# sirius1.net
KiCad netlist of a schematic drawn in EAGLE
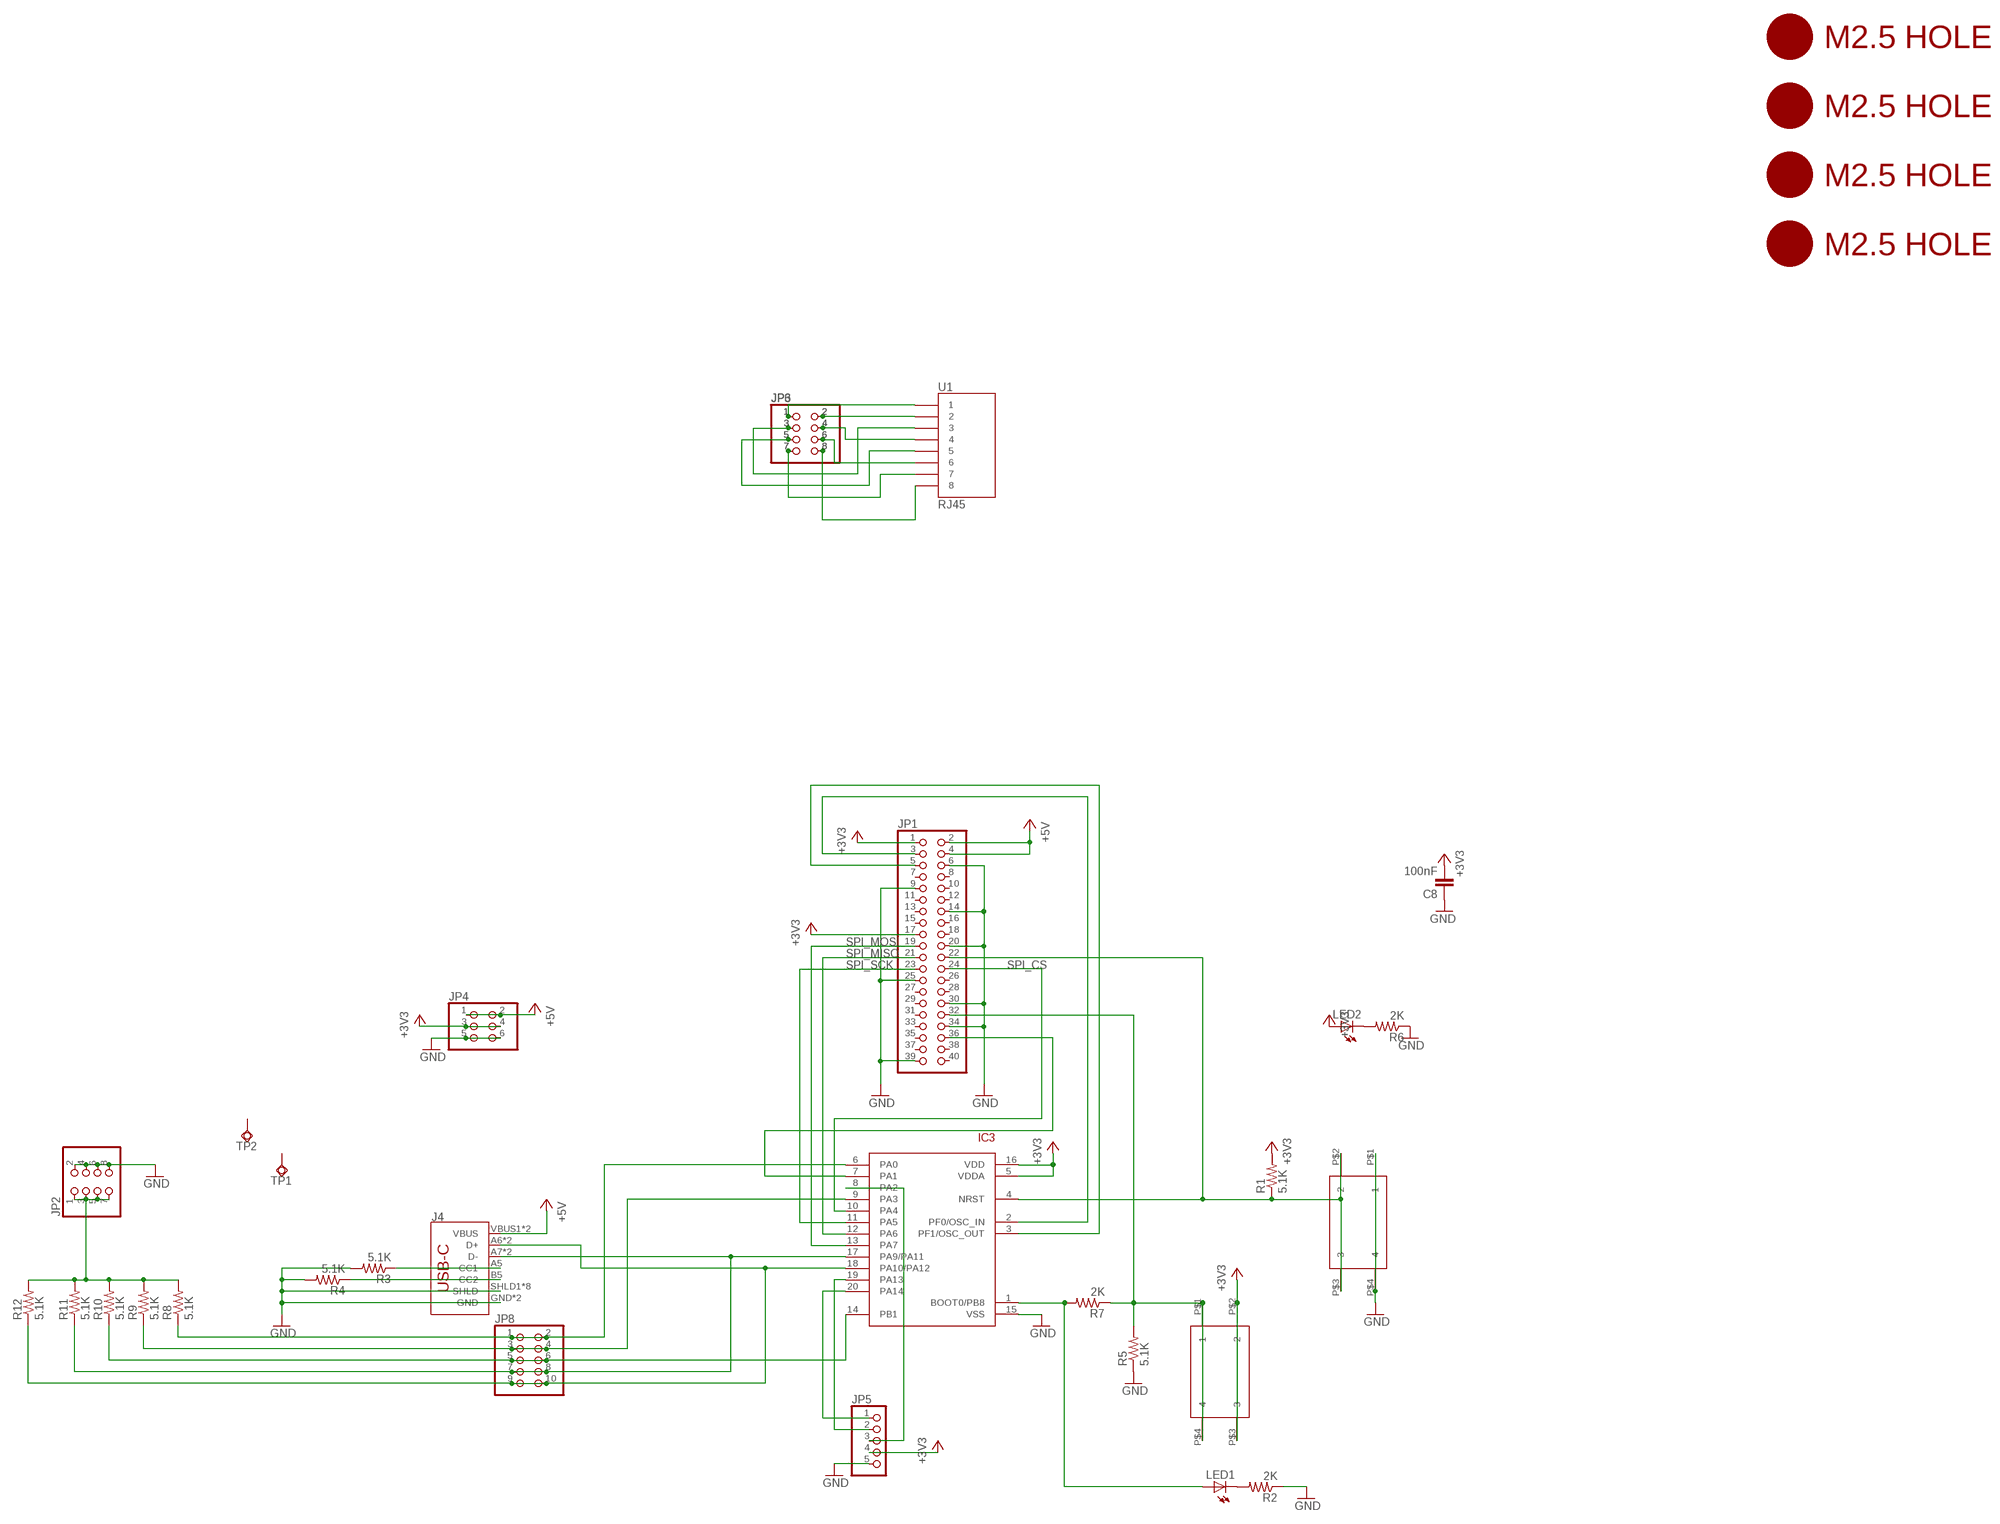
[diagram p0: schematic, sheet 1]

(export (version "E")
  (design (tool "Eeschema 10.0.6"))
  (components
    (comp (ref "C8")
      (value "100nF")
      (footprint "eagle-import:0805@1")
      (libsource (lib "eagle-import") (part "CAP0805"))
    )
    (comp (ref "IC3")
      (value "STM32F042F4")
      (footprint "eagle-import:TSSOP20")
      (libsource (lib "eagle-import") (part "STM32F042F4"))
    )
    (comp (ref "J4")
      (value "USB_C16PIN")
      (footprint "eagle-import:USB-C-16P")
      (libsource (lib "eagle-import") (part "USB_C16PIN"))
    )
    (comp (ref "JP1")
      (value "PINHD-2X20-BIG")
      (footprint "eagle-import:2X20-BIG")
      (libsource (lib "eagle-import") (part "PINHD-2X20-BIG"))
    )
    (comp (ref "JP2")
      (value "PINHD-2X4")
      (footprint "eagle-import:2X04")
      (libsource (lib "eagle-import") (part "PINHD-2X4"))
    )
    (comp (ref "JP3")
      (value "PINHD-2X4")
      (footprint "eagle-import:2X04")
      (libsource (lib "eagle-import") (part "PINHD-2X4"))
    )
    (comp (ref "JP4")
      (value "PINHD-2X3")
      (footprint "eagle-import:2X03")
      (libsource (lib "eagle-import") (part "PINHD-2X3"))
    )
    (comp (ref "JP5")
      (value "PINHD-1X5")
      (footprint "eagle-import:1X05")
      (libsource (lib "eagle-import") (part "PINHD-1X5"))
    )
    (comp (ref "JP6")
      (value "PINHD-2X4")
      (footprint "eagle-import:2X04")
      (libsource (lib "eagle-import") (part "PINHD-2X4"))
    )
    (comp (ref "JP8")
      (value "PINHD-2X5")
      (footprint "eagle-import:2X05")
      (libsource (lib "eagle-import") (part "PINHD-2X5"))
    )
    (comp (ref "LED1")
      (value "LEDCHIP-LED0805")
      (footprint "eagle-import:CHIP-LED0805")
      (libsource (lib "eagle-import") (part "LEDCHIP-LED0805"))
    )
    (comp (ref "LED2")
      (value "LEDCHIP-LED0805")
      (footprint "eagle-import:CHIP-LED0805")
      (libsource (lib "eagle-import") (part "LEDCHIP-LED0805"))
    )
    (comp (ref "R1")
      (value "5.1K")
      (footprint "eagle-import:0805")
      (libsource (lib "eagle-import") (part "RESISTOR0805-RES"))
    )
    (comp (ref "R2")
      (value "2K")
      (footprint "eagle-import:0805")
      (libsource (lib "eagle-import") (part "RESISTOR0805-RES"))
    )
    (comp (ref "R3")
      (value "5.1K")
      (footprint "eagle-import:0805")
      (libsource (lib "eagle-import") (part "RESISTOR0805-RES"))
    )
    (comp (ref "R4")
      (value "5.1K")
      (footprint "eagle-import:0805")
      (libsource (lib "eagle-import") (part "RESISTOR0805-RES"))
    )
    (comp (ref "R5")
      (value "5.1K")
      (footprint "eagle-import:0805")
      (libsource (lib "eagle-import") (part "RESISTOR0805-RES"))
    )
    (comp (ref "R6")
      (value "2K")
      (footprint "eagle-import:0805")
      (libsource (lib "eagle-import") (part "RESISTOR0805-RES"))
    )
    (comp (ref "R7")
      (value "2K")
      (footprint "eagle-import:0805")
      (libsource (lib "eagle-import") (part "RESISTOR0805-RES"))
    )
    (comp (ref "R8")
      (value "5.1K")
      (footprint "eagle-import:0805")
      (libsource (lib "eagle-import") (part "RESISTOR0805-RES"))
    )
    (comp (ref "R9")
      (value "5.1K")
      (footprint "eagle-import:0805")
      (libsource (lib "eagle-import") (part "RESISTOR0805-RES"))
    )
    (comp (ref "R10")
      (value "5.1K")
      (footprint "eagle-import:0805")
      (libsource (lib "eagle-import") (part "RESISTOR0805-RES"))
    )
    (comp (ref "R11")
      (value "5.1K")
      (footprint "eagle-import:0805")
      (libsource (lib "eagle-import") (part "RESISTOR0805-RES"))
    )
    (comp (ref "R12")
      (value "5.1K")
      (footprint "eagle-import:0805")
      (libsource (lib "eagle-import") (part "RESISTOR0805-RES"))
    )
    (comp (ref "SW1")
      (value "324_SW")
      (footprint "eagle-import:342_SWICH_FOOT")
      (libsource (lib "eagle-import") (part "324_SW"))
    )
    (comp (ref "SW4")
      (value "324_SW")
      (footprint "eagle-import:342_SWICH_FOOT")
      (libsource (lib "eagle-import") (part "324_SW"))
    )
    (comp (ref "TP1")
      (value "TPSQPAD1-20")
      (footprint "eagle-import:P1-20")
      (libsource (lib "eagle-import") (part "TPSQPAD1-20"))
    )
    (comp (ref "TP2")
      (value "TPSQPAD1-20")
      (footprint "eagle-import:P1-20")
      (libsource (lib "eagle-import") (part "TPSQPAD1-20"))
    )
    (comp (ref "U$2")
      (value "M2.5HOLE")
      (footprint "eagle-import:M2.5HOLE")
      (libsource (lib "eagle-import") (part "M2.5HOLE"))
    )
    (comp (ref "U$3")
      (value "M2.5HOLE")
      (footprint "eagle-import:M2.5HOLE")
      (libsource (lib "eagle-import") (part "M2.5HOLE"))
    )
    (comp (ref "U$4")
      (value "M2.5HOLE")
      (footprint "eagle-import:M2.5HOLE")
      (libsource (lib "eagle-import") (part "M2.5HOLE"))
    )
    (comp (ref "U$5")
      (value "M2.5HOLE")
      (footprint "eagle-import:M2.5HOLE")
      (libsource (lib "eagle-import") (part "M2.5HOLE"))
    )
    (comp (ref "U1")
      (value "RJ45")
      (footprint "eagle-import:RJ45-8")
      (libsource (lib "eagle-import") (part "RJ45-8PTH"))
    )
  )
  (nets
    (net (code "1") (name "+3V3") (class "Default")
      (node (ref "C8") (pin "2") (pinfunction "2_2") (pintype "passive"))
      (node (ref "IC3") (pin "16") (pinfunction "VDD_16") (pintype "bidirectional"))
      (node (ref "IC3") (pin "5") (pinfunction "VDDA_5") (pintype "bidirectional"))
      (node (ref "JP1") (pin "1") (pinfunction "1_1") (pintype "passive"))
      (node (ref "JP1") (pin "17") (pinfunction "17_17") (pintype "passive"))
      (node (ref "JP4") (pin "3") (pinfunction "3_3") (pintype "passive"))
      (node (ref "JP4") (pin "4") (pinfunction "4_4") (pintype "passive"))
      (node (ref "JP5") (pin "4") (pinfunction "4_4") (pintype "passive"))
      (node (ref "LED2") (pin "A") (pinfunction "A_A") (pintype "passive"))
      (node (ref "R1") (pin "2") (pinfunction "2_2") (pintype "passive"))
      (node (ref "SW1") (pin "P$2") (pinfunction "2_P$2") (pintype "bidirectional"))
      (node (ref "SW1") (pin "P$3") (pinfunction "3_P$3") (pintype "bidirectional"))
    )
    (net (code "2") (name "+5V") (class "Default")
      (node (ref "J4") (pin "VBUS1") (pinfunction "VBUS_VBUS1") (pintype "bidirectional"))
      (node (ref "J4") (pin "VBUS2") (pinfunction "VBUS_VBUS2") (pintype "bidirectional"))
      (node (ref "JP1") (pin "2") (pinfunction "2_2") (pintype "passive"))
      (node (ref "JP1") (pin "4") (pinfunction "4_4") (pintype "passive"))
      (node (ref "JP4") (pin "1") (pinfunction "1_1") (pintype "passive"))
      (node (ref "JP4") (pin "2") (pinfunction "2_2") (pintype "passive"))
    )
    (net (code "3") (name "/SPI_CS") (class "Default")
      (node (ref "IC3") (pin "10") (pinfunction "PA4_10") (pintype "bidirectional"))
      (node (ref "JP1") (pin "24") (pinfunction "24_24") (pintype "passive"))
    )
    (net (code "4") (name "/SPI_MISO") (class "Default")
      (node (ref "IC3") (pin "12") (pinfunction "PA6_12") (pintype "bidirectional"))
      (node (ref "JP1") (pin "21") (pinfunction "21_21") (pintype "passive"))
    )
    (net (code "5") (name "/SPI_MOSI") (class "Default")
      (node (ref "IC3") (pin "13") (pinfunction "PA7_13") (pintype "bidirectional"))
      (node (ref "JP1") (pin "19") (pinfunction "19_19") (pintype "passive"))
    )
    (net (code "6") (name "/SPI_SCK") (class "Default")
      (node (ref "IC3") (pin "11") (pinfunction "PA5_11") (pintype "bidirectional"))
      (node (ref "JP1") (pin "23") (pinfunction "23_23") (pintype "passive"))
    )
    (net (code "7") (name "GND") (class "Default")
      (node (ref "C8") (pin "1") (pinfunction "1_1") (pintype "passive"))
      (node (ref "IC3") (pin "15") (pinfunction "VSS_15") (pintype "bidirectional"))
      (node (ref "J4") (pin "GND") (pinfunction "GND_GND") (pintype "bidirectional"))
      (node (ref "J4") (pin "GND2") (pinfunction "GND_GND2") (pintype "bidirectional"))
      (node (ref "J4") (pin "SHLD1") (pinfunction "SHLD_SHLD1") (pintype "bidirectional"))
      (node (ref "J4") (pin "SHLD2") (pinfunction "SHLD_SHLD2") (pintype "bidirectional"))
      (node (ref "J4") (pin "SHLD3") (pinfunction "SHLD_SHLD3") (pintype "bidirectional"))
      (node (ref "J4") (pin "SHLD4") (pinfunction "SHLD_SHLD4") (pintype "bidirectional"))
      (node (ref "J4") (pin "SHLD5") (pinfunction "SHLD_SHLD5") (pintype "bidirectional"))
      (node (ref "J4") (pin "SHLD6") (pinfunction "SHLD_SHLD6") (pintype "bidirectional"))
      (node (ref "J4") (pin "SHLD7") (pinfunction "SHLD_SHLD7") (pintype "bidirectional"))
      (node (ref "J4") (pin "SHLD8") (pinfunction "SHLD_SHLD8") (pintype "bidirectional"))
      (node (ref "JP1") (pin "14") (pinfunction "14_14") (pintype "passive"))
      (node (ref "JP1") (pin "20") (pinfunction "20_20") (pintype "passive"))
      (node (ref "JP1") (pin "25") (pinfunction "25_25") (pintype "passive"))
      (node (ref "JP1") (pin "30") (pinfunction "30_30") (pintype "passive"))
      (node (ref "JP1") (pin "34") (pinfunction "34_34") (pintype "passive"))
      (node (ref "JP1") (pin "39") (pinfunction "39_39") (pintype "passive"))
      (node (ref "JP1") (pin "6") (pinfunction "6_6") (pintype "passive"))
      (node (ref "JP1") (pin "9") (pinfunction "9_9") (pintype "passive"))
      (node (ref "JP2") (pin "2") (pinfunction "2_2") (pintype "passive"))
      (node (ref "JP2") (pin "4") (pinfunction "4_4") (pintype "passive"))
      (node (ref "JP2") (pin "6") (pinfunction "6_6") (pintype "passive"))
      (node (ref "JP2") (pin "8") (pinfunction "8_8") (pintype "passive"))
      (node (ref "JP4") (pin "5") (pinfunction "5_5") (pintype "passive"))
      (node (ref "JP4") (pin "6") (pinfunction "6_6") (pintype "passive"))
      (node (ref "JP5") (pin "5") (pinfunction "5_5") (pintype "passive"))
      (node (ref "R2") (pin "1") (pinfunction "1_1") (pintype "passive"))
      (node (ref "R3") (pin "2") (pinfunction "2_2") (pintype "passive"))
      (node (ref "R4") (pin "2") (pinfunction "2_2") (pintype "passive"))
      (node (ref "R5") (pin "1") (pinfunction "1_1") (pintype "passive"))
      (node (ref "R6") (pin "1") (pinfunction "1_1") (pintype "passive"))
      (node (ref "SW4") (pin "P$1") (pinfunction "1_P$1") (pintype "bidirectional"))
      (node (ref "SW4") (pin "P$4") (pinfunction "4_P$4") (pintype "bidirectional"))
    )
    (net (code "8") (name "Net-(IC3-BOOT0{slash}PB8)") (class "Default")
      (node (ref "IC3") (pin "1") (pinfunction "BOOT0/PB8_1") (pintype "bidirectional"))
      (node (ref "LED1") (pin "A") (pinfunction "A_A") (pintype "passive"))
      (node (ref "R7") (pin "2") (pinfunction "2_2") (pintype "passive"))
    )
    (net (code "9") (name "Net-(IC3-NRST)") (class "Default")
      (node (ref "IC3") (pin "4") (pinfunction "NRST_4") (pintype "bidirectional"))
      (node (ref "JP1") (pin "22") (pinfunction "22_22") (pintype "passive"))
      (node (ref "R1") (pin "1") (pinfunction "1_1") (pintype "passive"))
      (node (ref "SW4") (pin "P$2") (pinfunction "2_P$2") (pintype "bidirectional"))
      (node (ref "SW4") (pin "P$3") (pinfunction "3_P$3") (pintype "bidirectional"))
    )
    (net (code "10") (name "Net-(IC3-PA0)") (class "Default")
      (node (ref "IC3") (pin "6") (pinfunction "PA0_6") (pintype "bidirectional"))
      (node (ref "JP8") (pin "1") (pinfunction "1_1") (pintype "passive"))
      (node (ref "JP8") (pin "2") (pinfunction "2_2") (pintype "passive"))
      (node (ref "R8") (pin "1") (pinfunction "1_1") (pintype "passive"))
    )
    (net (code "11") (name "Net-(IC3-PA1)") (class "Default")
      (node (ref "IC3") (pin "7") (pinfunction "PA1_7") (pintype "bidirectional"))
      (node (ref "JP1") (pin "36") (pinfunction "36_36") (pintype "passive"))
    )
    (net (code "12") (name "Net-(IC3-PA2)") (class "Default")
      (node (ref "IC3") (pin "8") (pinfunction "PA2_8") (pintype "bidirectional"))
      (node (ref "JP5") (pin "3") (pinfunction "3_3") (pintype "passive"))
    )
    (net (code "13") (name "Net-(IC3-PA3)") (class "Default")
      (node (ref "IC3") (pin "9") (pinfunction "PA3_9") (pintype "bidirectional"))
      (node (ref "JP8") (pin "3") (pinfunction "3_3") (pintype "passive"))
      (node (ref "JP8") (pin "4") (pinfunction "4_4") (pintype "passive"))
      (node (ref "R9") (pin "1") (pinfunction "1_1") (pintype "passive"))
    )
    (net (code "14") (name "Net-(IC3-PA9{slash}PA11)") (class "Default")
      (node (ref "IC3") (pin "17") (pinfunction "PA9/PA11_17") (pintype "bidirectional"))
      (node (ref "J4") (pin "A7") (pinfunction "D-_A7") (pintype "bidirectional"))
      (node (ref "J4") (pin "B7") (pinfunction "D-_B7") (pintype "bidirectional"))
      (node (ref "JP8") (pin "7") (pinfunction "7_7") (pintype "passive"))
      (node (ref "JP8") (pin "8") (pinfunction "8_8") (pintype "passive"))
      (node (ref "R11") (pin "1") (pinfunction "1_1") (pintype "passive"))
    )
    (net (code "15") (name "Net-(IC3-PA10{slash}PA12)") (class "Default")
      (node (ref "IC3") (pin "18") (pinfunction "PA10/PA12_18") (pintype "bidirectional"))
      (node (ref "J4") (pin "A6") (pinfunction "D+_A6") (pintype "bidirectional"))
      (node (ref "J4") (pin "B6") (pinfunction "D+_B6") (pintype "bidirectional"))
      (node (ref "JP8") (pin "10") (pinfunction "10_10") (pintype "passive"))
      (node (ref "JP8") (pin "9") (pinfunction "9_9") (pintype "passive"))
      (node (ref "R12") (pin "1") (pinfunction "1_1") (pintype "passive"))
    )
    (net (code "16") (name "Net-(IC3-PA13)") (class "Default")
      (node (ref "IC3") (pin "19") (pinfunction "PA13_19") (pintype "bidirectional"))
      (node (ref "JP5") (pin "2") (pinfunction "2_2") (pintype "passive"))
    )
    (net (code "17") (name "Net-(IC3-PA14)") (class "Default")
      (node (ref "IC3") (pin "20") (pinfunction "PA14_20") (pintype "bidirectional"))
      (node (ref "JP5") (pin "1") (pinfunction "1_1") (pintype "passive"))
    )
    (net (code "18") (name "Net-(IC3-PB1)") (class "Default")
      (node (ref "IC3") (pin "14") (pinfunction "PB1_14") (pintype "bidirectional"))
      (node (ref "JP8") (pin "5") (pinfunction "5_5") (pintype "passive"))
      (node (ref "JP8") (pin "6") (pinfunction "6_6") (pintype "passive"))
      (node (ref "R10") (pin "1") (pinfunction "1_1") (pintype "passive"))
    )
    (net (code "19") (name "Net-(IC3-PF0{slash}OSC_IN)") (class "Default")
      (node (ref "IC3") (pin "2") (pinfunction "PF0/OSC_IN_2") (pintype "bidirectional"))
      (node (ref "JP1") (pin "3") (pinfunction "3_3") (pintype "passive"))
    )
    (net (code "20") (name "Net-(IC3-PF1{slash}OSC_OUT)") (class "Default")
      (node (ref "IC3") (pin "3") (pinfunction "PF1/OSC_OUT_3") (pintype "bidirectional"))
      (node (ref "JP1") (pin "5") (pinfunction "5_5") (pintype "passive"))
    )
    (net (code "21") (name "Net-(J4-CC1)") (class "Default")
      (node (ref "J4") (pin "A5") (pinfunction "CC1_A5") (pintype "bidirectional"))
      (node (ref "R3") (pin "1") (pinfunction "1_1") (pintype "passive"))
    )
    (net (code "22") (name "Net-(J4-CC2)") (class "Default")
      (node (ref "J4") (pin "B5") (pinfunction "CC2_B5") (pintype "bidirectional"))
      (node (ref "R4") (pin "1") (pinfunction "1_1") (pintype "passive"))
    )
    (net (code "23") (name "Net-(JP2-Pad1)") (class "Default")
      (node (ref "JP2") (pin "1") (pinfunction "1_1") (pintype "passive"))
      (node (ref "JP2") (pin "3") (pinfunction "3_3") (pintype "passive"))
      (node (ref "JP2") (pin "5") (pinfunction "5_5") (pintype "passive"))
      (node (ref "JP2") (pin "7") (pinfunction "7_7") (pintype "passive"))
      (node (ref "R10") (pin "2") (pinfunction "2_2") (pintype "passive"))
      (node (ref "R11") (pin "2") (pinfunction "2_2") (pintype "passive"))
      (node (ref "R12") (pin "2") (pinfunction "2_2") (pintype "passive"))
      (node (ref "R8") (pin "2") (pinfunction "2_2") (pintype "passive"))
      (node (ref "R9") (pin "2") (pinfunction "2_2") (pintype "passive"))
    )
    (net (code "24") (name "Net-(JP3-Pad1)") (class "Default")
      (node (ref "JP3") (pin "1") (pinfunction "1_1") (pintype "passive"))
      (node (ref "JP6") (pin "1") (pinfunction "1_1") (pintype "passive"))
      (node (ref "U1") (pin "1") (pinfunction "1_1") (pintype "bidirectional"))
    )
    (net (code "25") (name "Net-(JP3-Pad2)") (class "Default")
      (node (ref "JP3") (pin "2") (pinfunction "2_2") (pintype "passive"))
      (node (ref "JP6") (pin "2") (pinfunction "2_2") (pintype "passive"))
      (node (ref "U1") (pin "2") (pinfunction "2_2") (pintype "bidirectional"))
    )
    (net (code "26") (name "Net-(JP3-Pad3)") (class "Default")
      (node (ref "JP3") (pin "3") (pinfunction "3_3") (pintype "passive"))
      (node (ref "JP6") (pin "3") (pinfunction "3_3") (pintype "passive"))
      (node (ref "U1") (pin "3") (pinfunction "3_3") (pintype "bidirectional"))
    )
    (net (code "27") (name "Net-(JP3-Pad4)") (class "Default")
      (node (ref "JP3") (pin "4") (pinfunction "4_4") (pintype "passive"))
      (node (ref "JP6") (pin "4") (pinfunction "4_4") (pintype "passive"))
      (node (ref "U1") (pin "4") (pinfunction "4_4") (pintype "bidirectional"))
    )
    (net (code "28") (name "Net-(JP3-Pad5)") (class "Default")
      (node (ref "JP3") (pin "5") (pinfunction "5_5") (pintype "passive"))
      (node (ref "JP6") (pin "5") (pinfunction "5_5") (pintype "passive"))
      (node (ref "U1") (pin "5") (pinfunction "5_5") (pintype "bidirectional"))
    )
    (net (code "29") (name "Net-(JP3-Pad6)") (class "Default")
      (node (ref "JP3") (pin "6") (pinfunction "6_6") (pintype "passive"))
      (node (ref "JP6") (pin "6") (pinfunction "6_6") (pintype "passive"))
      (node (ref "U1") (pin "6") (pinfunction "6_6") (pintype "bidirectional"))
    )
    (net (code "30") (name "Net-(JP3-Pad7)") (class "Default")
      (node (ref "JP3") (pin "7") (pinfunction "7_7") (pintype "passive"))
      (node (ref "JP6") (pin "7") (pinfunction "7_7") (pintype "passive"))
      (node (ref "U1") (pin "7") (pinfunction "7_7") (pintype "bidirectional"))
    )
    (net (code "31") (name "Net-(JP3-Pad8)") (class "Default")
      (node (ref "JP3") (pin "8") (pinfunction "8_8") (pintype "passive"))
      (node (ref "JP6") (pin "8") (pinfunction "8_8") (pintype "passive"))
      (node (ref "U1") (pin "8") (pinfunction "8_8") (pintype "bidirectional"))
    )
    (net (code "32") (name "Net-(LED1-PadC)") (class "Default")
      (node (ref "LED1") (pin "C") (pinfunction "C_C") (pintype "passive"))
      (node (ref "R2") (pin "2") (pinfunction "2_2") (pintype "passive"))
    )
    (net (code "33") (name "Net-(LED2-PadC)") (class "Default")
      (node (ref "LED2") (pin "C") (pinfunction "C_C") (pintype "passive"))
      (node (ref "R6") (pin "2") (pinfunction "2_2") (pintype "passive"))
    )
    (net (code "34") (name "Net-(SW1-1)") (class "Default")
      (node (ref "JP1") (pin "32") (pinfunction "32_32") (pintype "passive"))
      (node (ref "R5") (pin "2") (pinfunction "2_2") (pintype "passive"))
      (node (ref "R7") (pin "1") (pinfunction "1_1") (pintype "passive"))
      (node (ref "SW1") (pin "P$1") (pinfunction "1_P$1") (pintype "bidirectional"))
      (node (ref "SW1") (pin "P$4") (pinfunction "4_P$4") (pintype "bidirectional"))
    )
    (net (code "35") (name "unconnected-(JP1-Pad7)") (class "Default")
      (node (ref "JP1") (pin "7") (pinfunction "7_7") (pintype "passive"))
    )
    (net (code "36") (name "unconnected-(JP1-Pad8)") (class "Default")
      (node (ref "JP1") (pin "8") (pinfunction "8_8") (pintype "passive"))
    )
    (net (code "37") (name "unconnected-(JP1-Pad10)") (class "Default")
      (node (ref "JP1") (pin "10") (pinfunction "10_10") (pintype "passive"))
    )
    (net (code "38") (name "unconnected-(JP1-Pad11)") (class "Default")
      (node (ref "JP1") (pin "11") (pinfunction "11_11") (pintype "passive"))
    )
    (net (code "39") (name "unconnected-(JP1-Pad12)") (class "Default")
      (node (ref "JP1") (pin "12") (pinfunction "12_12") (pintype "passive"))
    )
    (net (code "40") (name "unconnected-(JP1-Pad13)") (class "Default")
      (node (ref "JP1") (pin "13") (pinfunction "13_13") (pintype "passive"))
    )
    (net (code "41") (name "unconnected-(JP1-Pad15)") (class "Default")
      (node (ref "JP1") (pin "15") (pinfunction "15_15") (pintype "passive"))
    )
    (net (code "42") (name "unconnected-(JP1-Pad16)") (class "Default")
      (node (ref "JP1") (pin "16") (pinfunction "16_16") (pintype "passive"))
    )
    (net (code "43") (name "unconnected-(JP1-Pad18)") (class "Default")
      (node (ref "JP1") (pin "18") (pinfunction "18_18") (pintype "passive"))
    )
    (net (code "44") (name "unconnected-(JP1-Pad26)") (class "Default")
      (node (ref "JP1") (pin "26") (pinfunction "26_26") (pintype "passive"))
    )
    (net (code "45") (name "unconnected-(JP1-Pad27)") (class "Default")
      (node (ref "JP1") (pin "27") (pinfunction "27_27") (pintype "passive"))
    )
    (net (code "46") (name "unconnected-(JP1-Pad28)") (class "Default")
      (node (ref "JP1") (pin "28") (pinfunction "28_28") (pintype "passive"))
    )
    (net (code "47") (name "unconnected-(JP1-Pad29)") (class "Default")
      (node (ref "JP1") (pin "29") (pinfunction "29_29") (pintype "passive"))
    )
    (net (code "48") (name "unconnected-(JP1-Pad31)") (class "Default")
      (node (ref "JP1") (pin "31") (pinfunction "31_31") (pintype "passive"))
    )
    (net (code "49") (name "unconnected-(JP1-Pad33)") (class "Default")
      (node (ref "JP1") (pin "33") (pinfunction "33_33") (pintype "passive"))
    )
    (net (code "50") (name "unconnected-(JP1-Pad35)") (class "Default")
      (node (ref "JP1") (pin "35") (pinfunction "35_35") (pintype "passive"))
    )
    (net (code "51") (name "unconnected-(JP1-Pad37)") (class "Default")
      (node (ref "JP1") (pin "37") (pinfunction "37_37") (pintype "passive"))
    )
    (net (code "52") (name "unconnected-(JP1-Pad38)") (class "Default")
      (node (ref "JP1") (pin "38") (pinfunction "38_38") (pintype "passive"))
    )
    (net (code "53") (name "unconnected-(JP1-Pad40)") (class "Default")
      (node (ref "JP1") (pin "40") (pinfunction "40_40") (pintype "passive"))
    )
    (net (code "54") (name "unconnected-(TP1-PadTP)") (class "Default")
      (node (ref "TP1") (pin "TP") (pinfunction "TP_TP") (pintype "input"))
    )
    (net (code "55") (name "unconnected-(TP2-PadTP)") (class "Default")
      (node (ref "TP2") (pin "TP") (pinfunction "TP_TP") (pintype "input"))
    )
  )
)
